# SCH_QC_Trigger_2022-11-12.net
KiCad netlist of a schematic drawn in EasyEDA
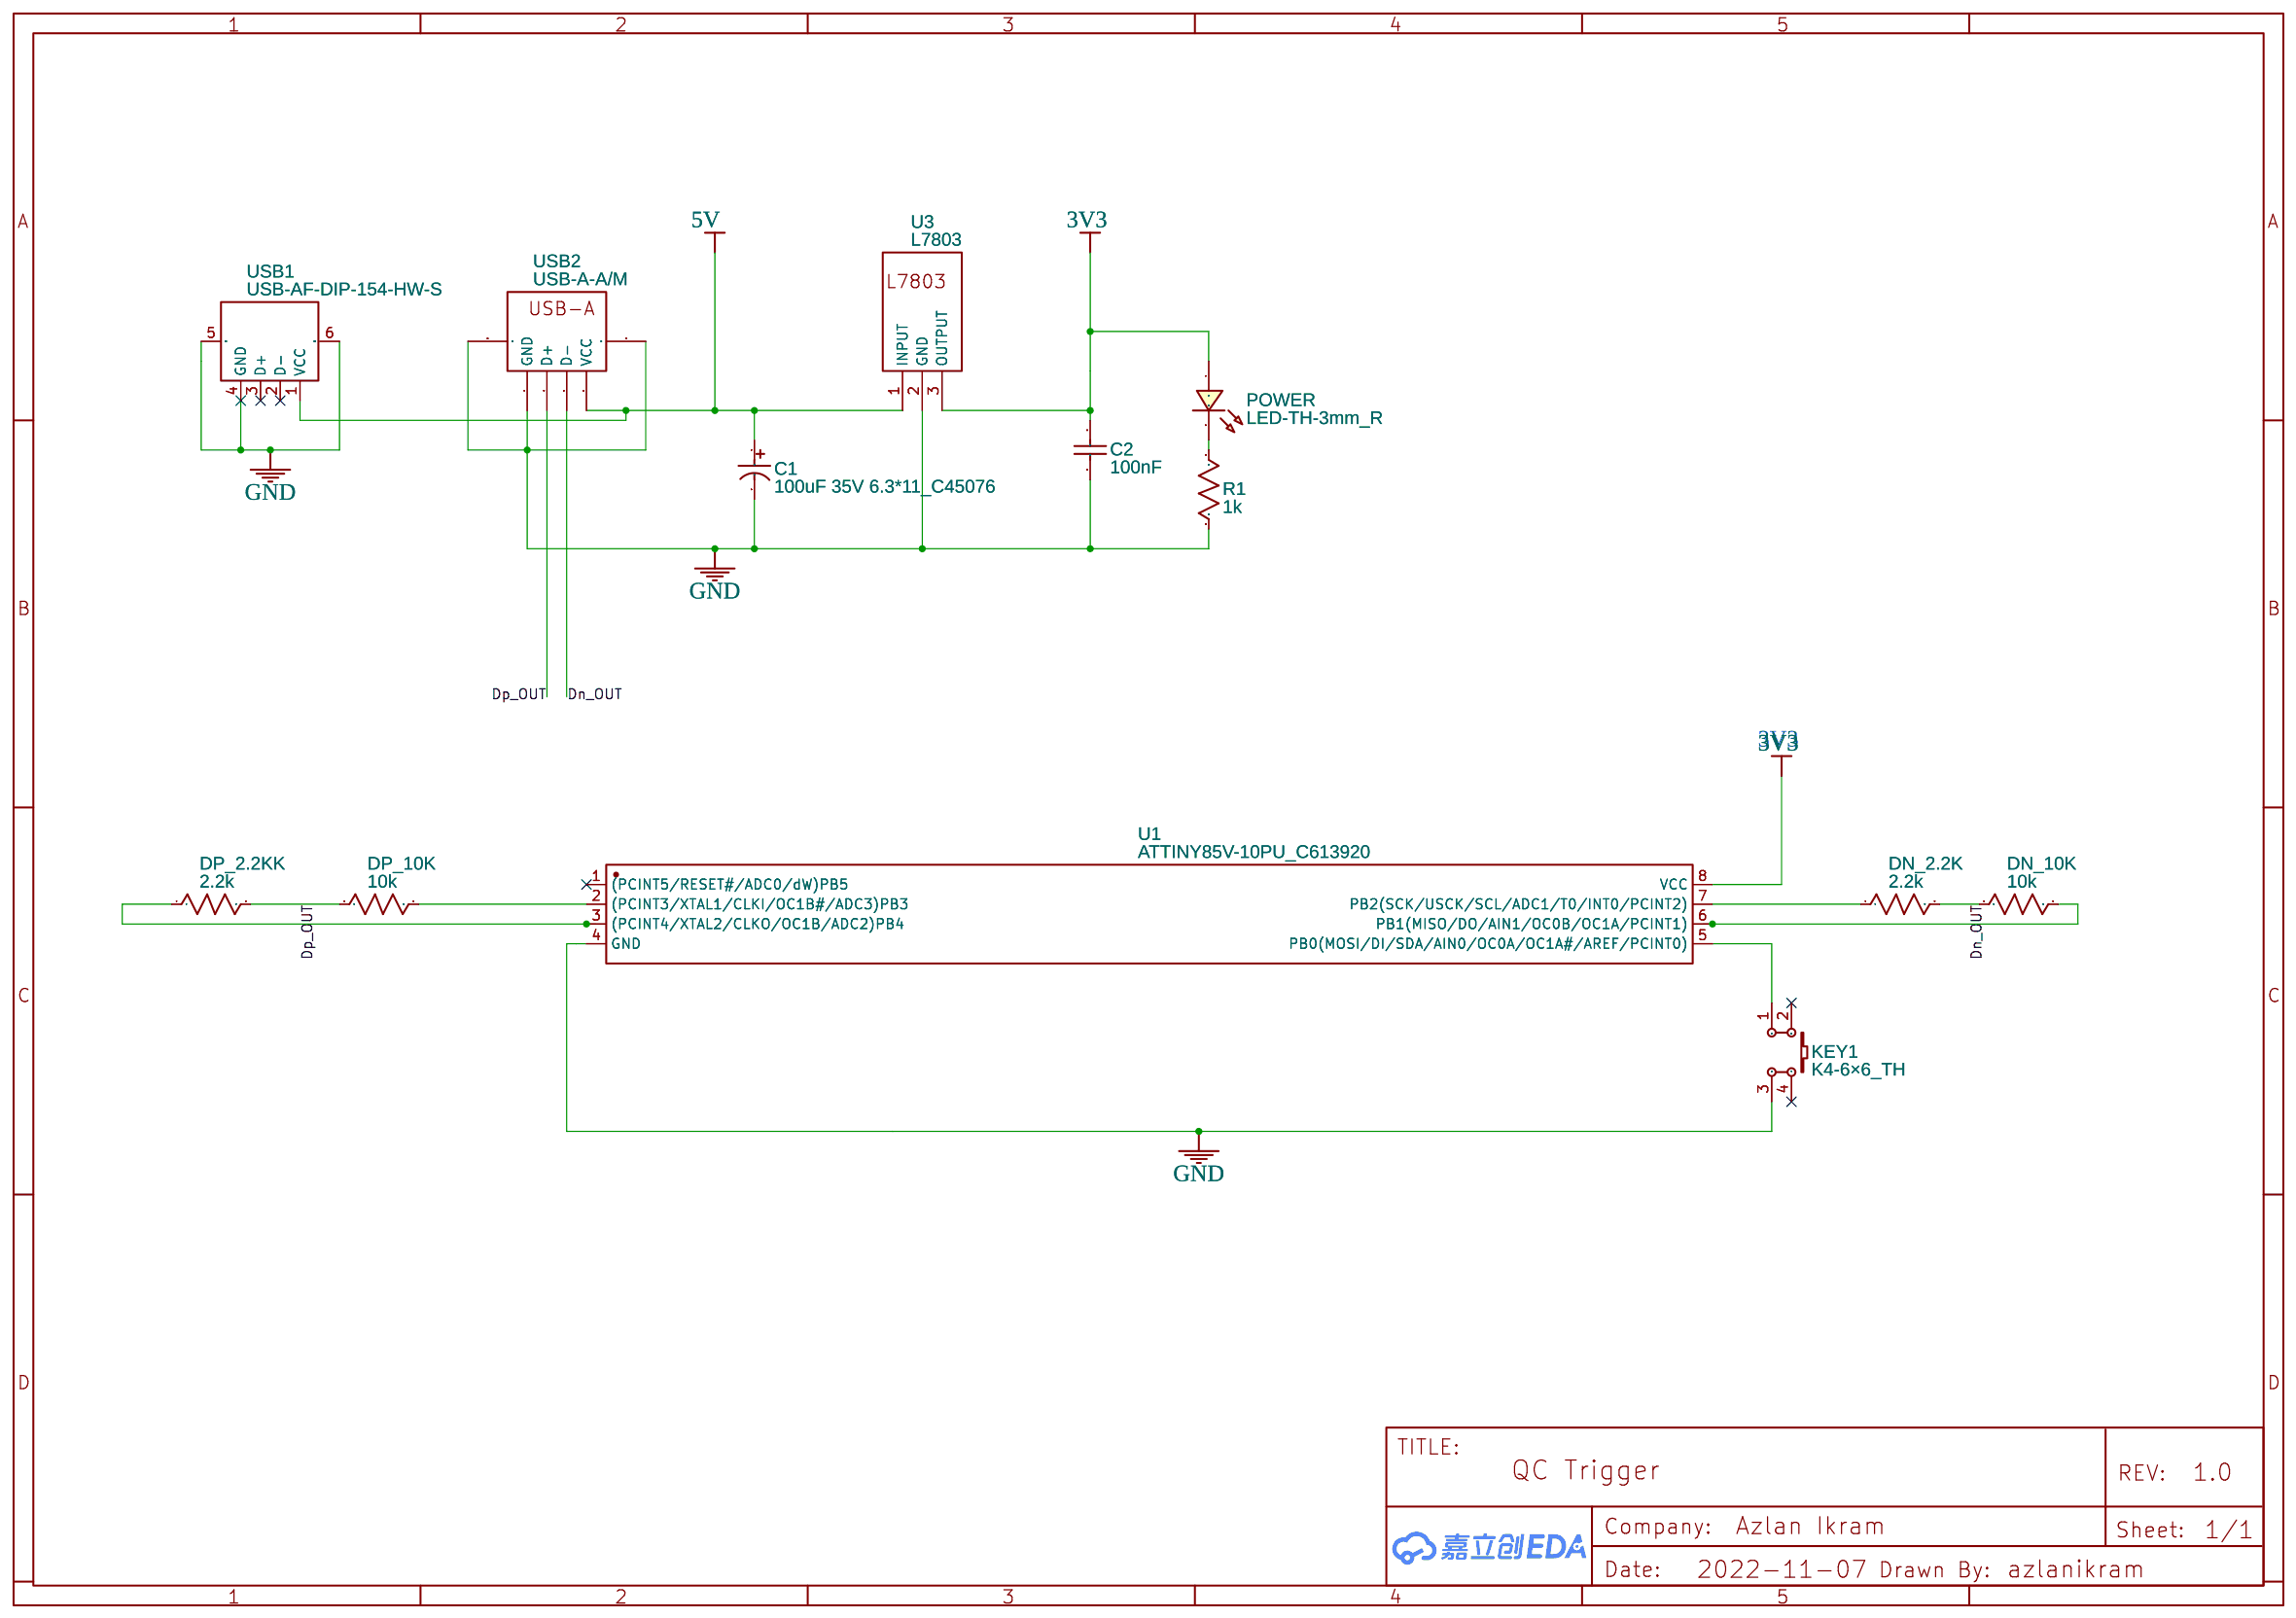
[diagram p0: schematic sheet]

(export (version "E")
  (design (tool "Eeschema 10.0.6"))
  (components
    (comp (ref "C1")
      (value "100uF 35V 6.3*11_C45076")
      (fields
        (field (name "BOM_Manufacturer Part") "100uF 35V 6.3*11")
        (field (name "BOM_Supplier Part") "C45076")
      )
      (libsource (lib "") (part "100uF 35V 6.3*11_C45076"))
    )
    (comp (ref "C2")
      (value "100nF")
      (fields (field (name "BOM_Manufacturer Part") "104J 100V") (field (name "BOM_Supplier Part") "C13547"))
      (libsource (lib "") (part "104J 100V"))
    )
    (comp (ref "DN_2.2K") (value "2.2k") (libsource (lib "") (part "R_AXIAL-0.5_US_2")))
    (comp (ref "DN_10K") (value "10k") (libsource (lib "") (part "R_AXIAL-0.5_US")))
    (comp (ref "DP_2.2KK") (value "2.2k") (libsource (lib "") (part "R_AXIAL-0.5_US_1")))
    (comp (ref "DP_10K") (value "10k") (libsource (lib "") (part "R_AXIAL-0.5_US_3")))
    (comp (ref "KEY1")
      (value "K4-6×6_TH")
      (fields
        (field (name "BOM_Manufacturer Part") "K2-1102DP-E4SW-04")
        (field (name "BOM_Supplier Part") "C136684")
      )
      (libsource (lib "") (part "K4-6×6_TH"))
    )
    (comp (ref "POWER")
      (value "LED-TH-3mm_R")
      (fields
        (field (name "BOM_Manufacturer Part") "204-10SDRD/S530-A3-L")
        (field (name "BOM_Supplier Part") "C84774")
      )
      (libsource (lib "") (part "LED-TH-3mm_R"))
    )
    (comp (ref "R1") (value "1k") (libsource (lib "") (part "R_AXIAL-0.5_US_4")))
    (comp (ref "U1")
      (value "ATTINY85V-10PU_C613920")
      (fields
        (field (name "BOM_Manufacturer Part") "ATTINY85V-10PU")
        (field (name "BOM_Supplier Part") "C613920")
      )
      (libsource (lib "") (part "ATTINY85V-10PU_C613920"))
    )
    (comp (ref "U3") (value "L7803") (libsource (lib "") (part "L7803")))
    (comp (ref "USB1")
      (value "USB-AF-DIP-154-HW-S")
      (fields (field (name "BOM_Supplier Part") "C2904892"))
      (libsource (lib "") (part "USB-AF-DIP-154-HW-S"))
    )
    (comp (ref "USB2")
      (value "USB-A-A/M")
      (fields
        (field (name "BOM_Manufacturer Part") "A/M Stick plate bent legs VinylPBT With a column")
        (field (name "BOM_Supplier Part") "C46394")
      )
      (libsource (lib "") (part "USB-A-A/M Stick plate bent legs VinylPBT With a column"))
    )
  )
  (nets
    (net (code "1") (name "/Dn_OUT") (class "Default")
      (node (ref "DN_10K") (pin "1") (pinfunction "1_1") (pintype "unspecified"))
      (node (ref "DN_2.2K") (pin "2") (pinfunction "2_2") (pintype "unspecified"))
      (node (ref "USB2") (pin "2") (pinfunction "D-_2") (pintype "input"))
    )
    (net (code "2") (name "/Dp_OUT") (class "Default")
      (node (ref "DP_10K") (pin "1") (pinfunction "1_1") (pintype "unspecified"))
      (node (ref "DP_2.2KK") (pin "2") (pinfunction "2_2") (pintype "unspecified"))
      (node (ref "USB2") (pin "3") (pinfunction "D+_3") (pintype "input"))
    )
    (net (code "3") (name "3V3") (class "Default")
      (node (ref "C2") (pin "2") (pinfunction "2_2") (pintype "input"))
      (node (ref "POWER") (pin "1") (pinfunction "1_1") (pintype "unspecified"))
      (node (ref "U1") (pin "8") (pinfunction "VCC_8") (pintype "unspecified"))
      (node (ref "U3") (pin "3") (pinfunction "OUTPUT_3") (pintype "unspecified"))
    )
    (net (code "4") (name "5V") (class "Default")
      (node (ref "C1") (pin "1") (pinfunction "1_1") (pintype "input"))
      (node (ref "U3") (pin "1") (pinfunction "INPUT_1") (pintype "unspecified"))
      (node (ref "USB1") (pin "1") (pinfunction "VCC_1") (pintype "input"))
      (node (ref "USB2") (pin "1") (pinfunction "VCC_1") (pintype "input"))
    )
    (net (code "5") (name "GND") (class "Default")
      (node (ref "C1") (pin "2") (pinfunction "2_2") (pintype "input"))
      (node (ref "C2") (pin "1") (pinfunction "1_1") (pintype "input"))
      (node (ref "KEY1") (pin "3") (pinfunction "3_3") (pintype "unspecified"))
      (node (ref "R1") (pin "2") (pinfunction "2_2") (pintype "unspecified"))
      (node (ref "U1") (pin "4") (pinfunction "GND_4") (pintype "unspecified"))
      (node (ref "U3") (pin "2") (pinfunction "GND_2") (pintype "unspecified"))
      (node (ref "USB1") (pin "4") (pinfunction "GND_4") (pintype "input"))
      (node (ref "USB1") (pin "5") (pinfunction "SH1_5") (pintype "unspecified"))
      (node (ref "USB1") (pin "6") (pinfunction "SH2_6") (pintype "unspecified"))
      (node (ref "USB2") (pin "4") (pinfunction "GND_4") (pintype "input"))
      (node (ref "USB2") (pin "5") (pinfunction "5_5") (pintype "unspecified"))
      (node (ref "USB2") (pin "6") (pinfunction "6_6") (pintype "unspecified"))
    )
    (net (code "6") (name "Net-(POWER-Pad2)") (class "Default")
      (node (ref "POWER") (pin "2") (pinfunction "2_2") (pintype "unspecified"))
      (node (ref "R1") (pin "1") (pinfunction "1_1") (pintype "unspecified"))
    )
    (net (code "7") (name "Net-(U1-(PCINT3{slash}XTAL1{slash}CLKI{slash}OC1B#{slash}ADC3)PB3)") (class "Default")
      (node (ref "DP_10K") (pin "2") (pinfunction "2_2") (pintype "unspecified"))
      (node (ref "U1") (pin "2") (pinfunction "(PCINT3/XTAL1/CLKI/OC1B#/ADC3)PB3_2") (pintype "unspecified"))
    )
    (net (code "8") (name "Net-(U1-(PCINT4{slash}XTAL2{slash}CLKO{slash}OC1B{slash}ADC2)PB4)") (class "Default")
      (node (ref "DP_2.2KK") (pin "1") (pinfunction "1_1") (pintype "unspecified"))
      (node (ref "U1") (pin "3") (pinfunction "(PCINT4/XTAL2/CLKO/OC1B/ADC2)PB4_3") (pintype "unspecified"))
    )
    (net (code "9") (name "Net-(U1-PB0(MOSI{slash}DI{slash}SDA{slash}AIN0{slash}OC0A{slash}OC1A#{slash}AREF{slash}PCINT0))") (class "Default")
      (node (ref "KEY1") (pin "1") (pinfunction "1_1") (pintype "unspecified"))
      (node (ref "U1") (pin "5") (pinfunction "PB0(MOSI/DI/SDA/AIN0/OC0A/OC1A#/AREF/PCINT0)_5") (pintype "unspecified"))
    )
    (net (code "10") (name "Net-(U1-PB1(MISO{slash}DO{slash}AIN1{slash}OC0B{slash}OC1A{slash}PCINT1))") (class "Default")
      (node (ref "DN_10K") (pin "2") (pinfunction "2_2") (pintype "unspecified"))
      (node (ref "U1") (pin "6") (pinfunction "PB1(MISO/DO/AIN1/OC0B/OC1A/PCINT1)_6") (pintype "unspecified"))
    )
    (net (code "11") (name "Net-(U1-PB2(SCK{slash}USCK{slash}SCL{slash}ADC1{slash}T0{slash}INT0{slash}PCINT2))") (class "Default")
      (node (ref "DN_2.2K") (pin "1") (pinfunction "1_1") (pintype "unspecified"))
      (node (ref "U1") (pin "7") (pinfunction "PB2(SCK/USCK/SCL/ADC1/T0/INT0/PCINT2)_7") (pintype "unspecified"))
    )
    (net (code "12") (name "unconnected-(KEY1-Pad2)") (class "Default")
      (node (ref "KEY1") (pin "2") (pinfunction "2_2") (pintype "unspecified+no_connect"))
    )
    (net (code "13") (name "unconnected-(KEY1-Pad4)") (class "Default")
      (node (ref "KEY1") (pin "4") (pinfunction "4_4") (pintype "unspecified+no_connect"))
    )
    (net (code "14") (name "unconnected-(U1-(PCINT5{slash}RESET#{slash}ADC0{slash}dW)PB5-Pad1)") (class "Default")
      (node (ref "U1") (pin "1") (pinfunction "(PCINT5/RESET#/ADC0/dW)PB5_1") (pintype "unspecified+no_connect"))
    )
    (net (code "15") (name "unconnected-(USB1-D+-Pad3)") (class "Default")
      (node (ref "USB1") (pin "3") (pinfunction "D+_3") (pintype "input+no_connect"))
    )
    (net (code "16") (name "unconnected-(USB1-D--Pad2)") (class "Default")
      (node (ref "USB1") (pin "2") (pinfunction "D-_2") (pintype "input+no_connect"))
    )
  )
)
